# Card_Edge_Connecgtor.net
KiCad netlist of a schematic drawn in Altium Designer
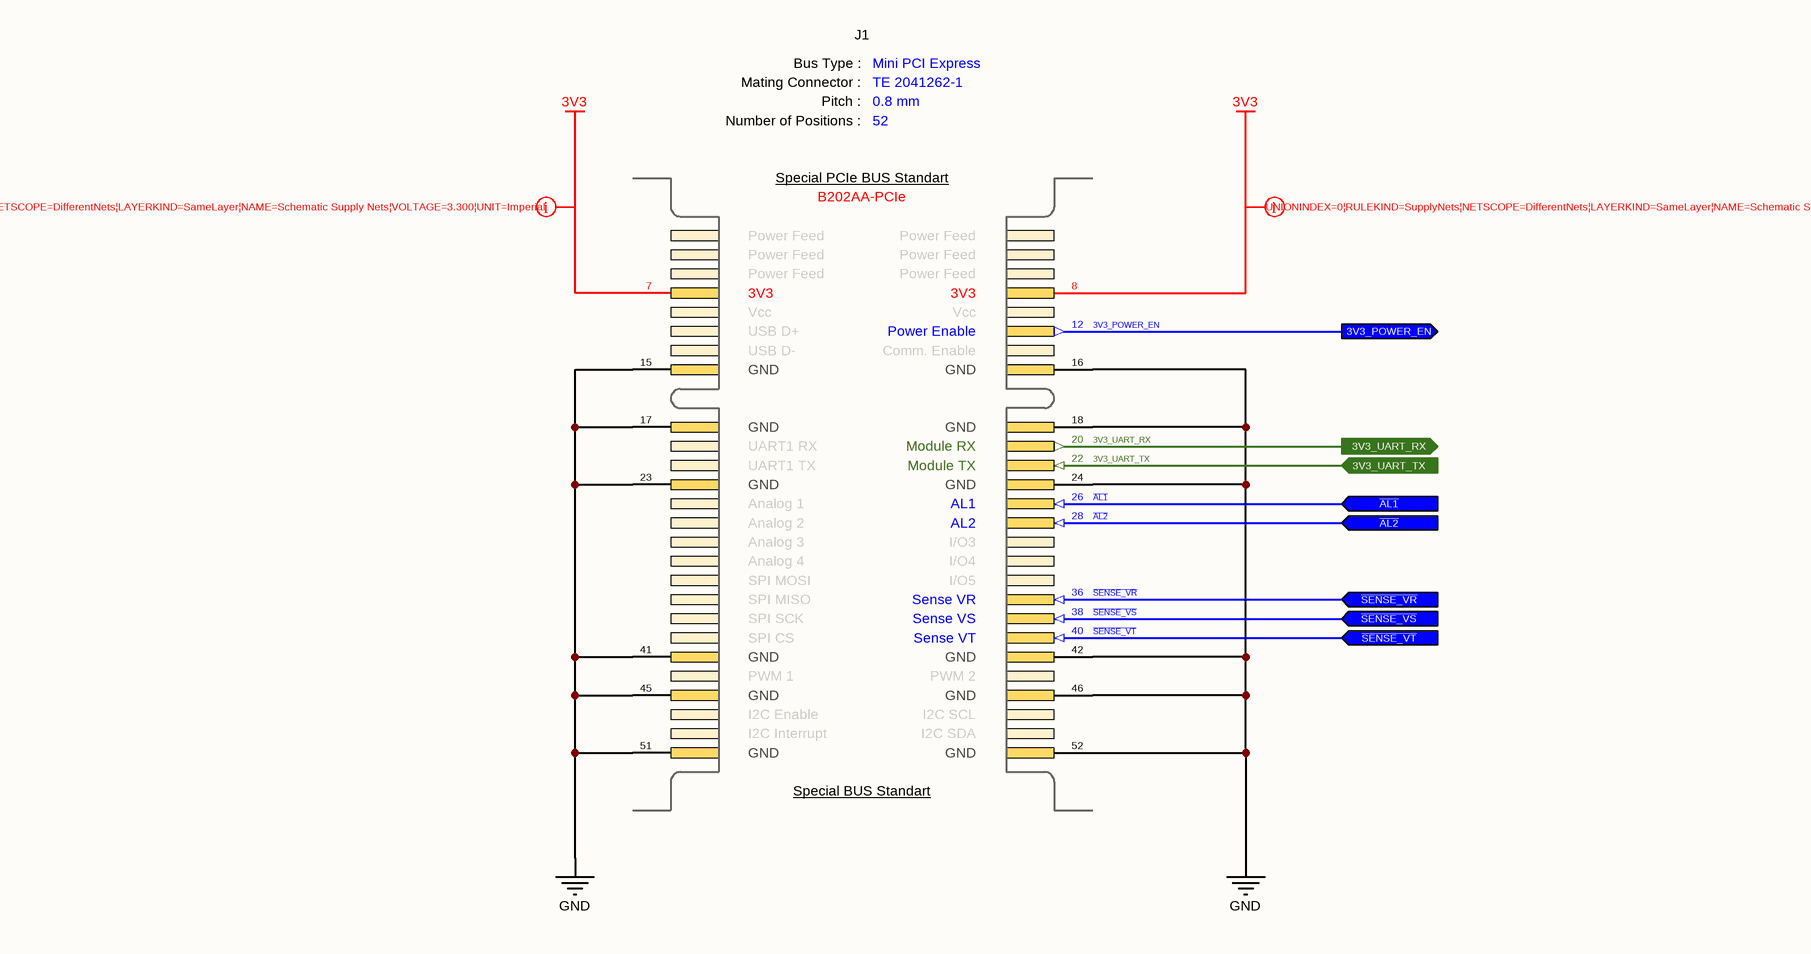
[diagram p0: Card Edge Connecgtor.SchDoc]

(export (version "E")
  (design (tool "Eeschema 10.0.6"))
  (components
    (comp (ref "J1")
      (value "Connector - Mini PCI-E (Male B202AA-PCIe)")
      (footprint "PCB - Mini PCI Express")
      (description "Mini PCI-Express gold finger connector.")
      (fields
        (field (name "BUS TYPE") "Mini PCI Express")
        (field (name "MATING CONNECTOR") "TE 2041262-1")
        (field (name "PITCH") "0.8 mm")
        (field (name "NUMBER OF POSITIONS") "52")
      )
      (libsource (lib "Akkoyun") (part "Connector - Mini PCI-E (Male B202AA-PCIe)"))
    )
  )
  (nets
    (net (code "1") (name "/3V3_POWER_EN") (class "Default")
      (node (ref "J1") (pin "12") (pinfunction "Pin-12_12") (pintype "output"))
    )
    (net (code "2") (name "/3V3_UART_RX") (class "Default")
      (node (ref "J1") (pin "20") (pinfunction "Pin-20_20") (pintype "output"))
    )
    (net (code "3") (name "/3V3_UART_TX") (class "Default")
      (node (ref "J1") (pin "22") (pinfunction "Pin-22_22") (pintype "input"))
    )
    (net (code "4") (name "/~{AL1}") (class "Default")
      (node (ref "J1") (pin "26") (pinfunction "Pin-26_26") (pintype "input"))
    )
    (net (code "5") (name "/~{AL2}") (class "Default")
      (node (ref "J1") (pin "28") (pinfunction "Pin-28_28") (pintype "input"))
    )
    (net (code "6") (name "/~{SENSE_VR}") (class "Default")
      (node (ref "J1") (pin "36") (pinfunction "Pin-36_36") (pintype "input"))
    )
    (net (code "7") (name "/~{SENSE_VS}") (class "Default")
      (node (ref "J1") (pin "38") (pinfunction "Pin-38_38") (pintype "input"))
    )
    (net (code "8") (name "/~{SENSE_VT}") (class "Default")
      (node (ref "J1") (pin "40") (pinfunction "Pin-40_40") (pintype "input"))
    )
    (net (code "9") (name "3V3") (class "Default")
      (node (ref "J1") (pin "7") (pinfunction "Pin-7_7") (pintype "power_in"))
      (node (ref "J1") (pin "8") (pinfunction "Pin-8_8") (pintype "power_in"))
    )
    (net (code "10") (name "GND") (class "Default")
      (node (ref "J1") (pin "15") (pinfunction "Pin-15_15") (pintype "power_in"))
      (node (ref "J1") (pin "16") (pinfunction "Pin-16_16") (pintype "power_in"))
      (node (ref "J1") (pin "17") (pinfunction "Pin-17_17") (pintype "power_in"))
      (node (ref "J1") (pin "18") (pinfunction "Pin-18_18") (pintype "power_in"))
      (node (ref "J1") (pin "23") (pinfunction "Pin-23_23") (pintype "power_in"))
      (node (ref "J1") (pin "24") (pinfunction "Pin-24_24") (pintype "power_in"))
      (node (ref "J1") (pin "41") (pinfunction "Pin-41_41") (pintype "power_in"))
      (node (ref "J1") (pin "42") (pinfunction "Pin-42_42") (pintype "power_in"))
      (node (ref "J1") (pin "45") (pinfunction "Pin-45_45") (pintype "power_in"))
      (node (ref "J1") (pin "46") (pinfunction "Pin-46_46") (pintype "power_in"))
      (node (ref "J1") (pin "51") (pinfunction "Pin-51_51") (pintype "power_in"))
      (node (ref "J1") (pin "52") (pinfunction "Pin-52_52") (pintype "power_in"))
    )
  )
)
